# power.net
KiCad netlist of a schematic drawn in Altium Designer
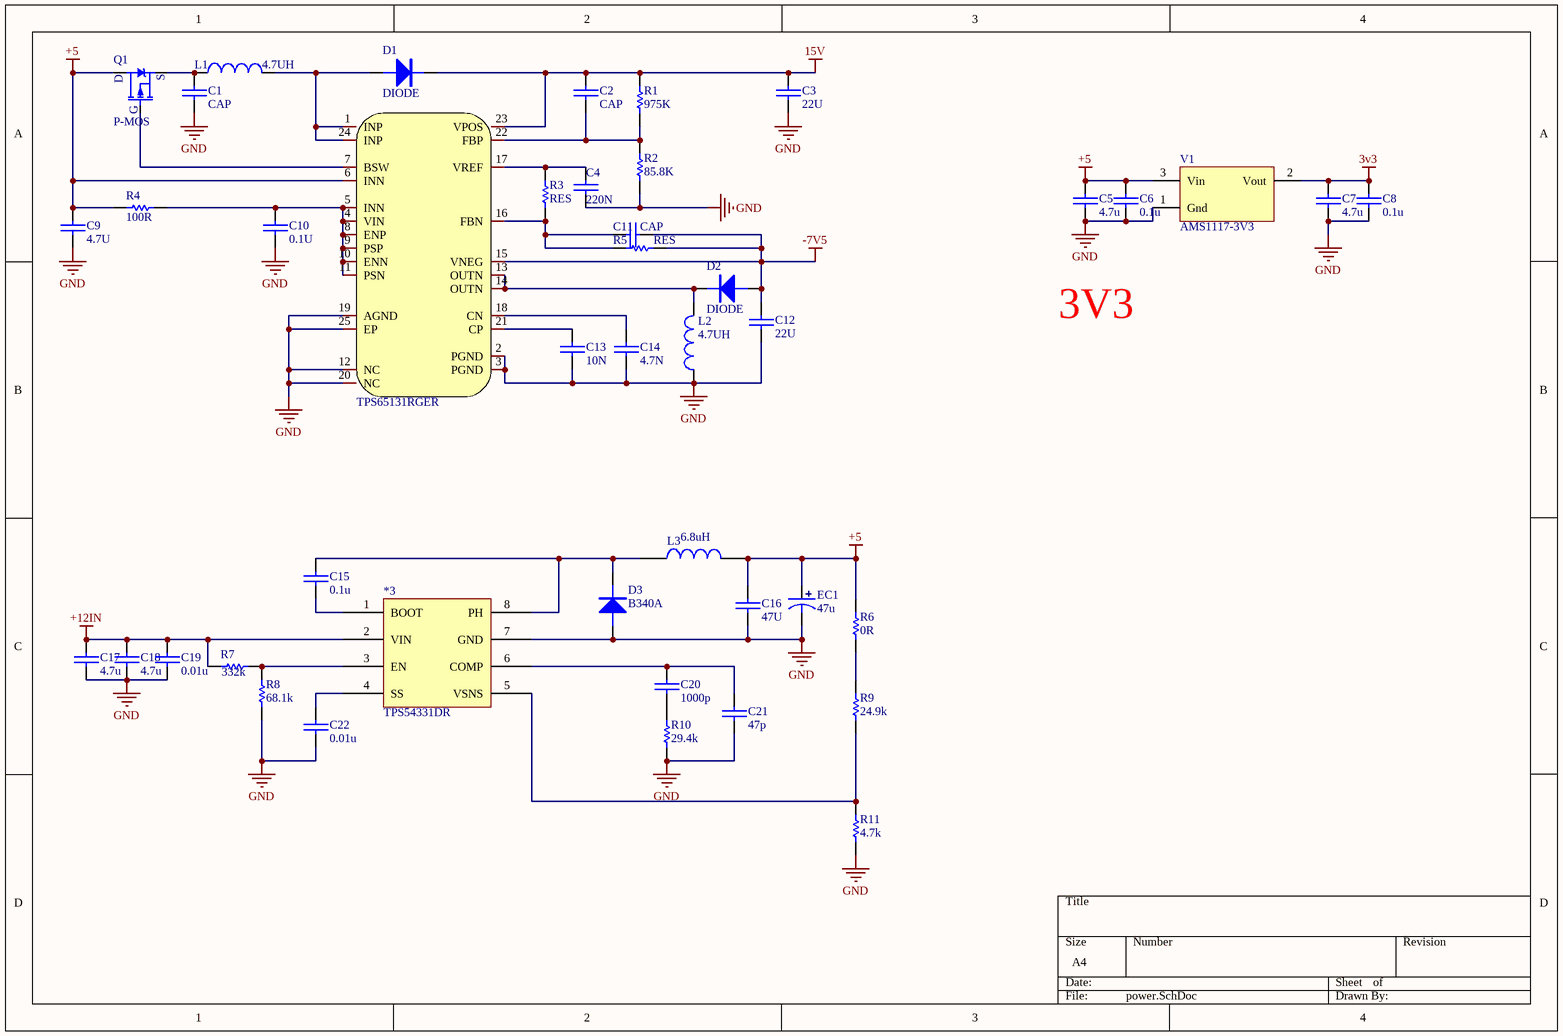
[diagram p0: power.SchDoc]

(export (version "E")
  (design (tool "Eeschema 10.0.6"))
  (components
    (comp (ref "*3")
      (value "TPS54331DR")
      (footprint "SOIC-8")
      (description "降压型DC-DC")
      (libsource (lib "0.03电源") (part "TPS54331DR"))
    )
    (comp (ref "C1")
      (value "CAP")
      (footprint "0603C")
      (description "无极性电容")
      (libsource (lib "1.00-阻容感") (part "CAP"))
    )
    (comp (ref "C2")
      (value "CAP")
      (footprint "0603C")
      (description "无极性电容")
      (libsource (lib "1.00-阻容感") (part "CAP"))
    )
    (comp (ref "C3")
      (value "22U")
      (footprint "0603C")
      (description "无极性电容")
      (libsource (lib "1.00-阻容感") (part "CAP"))
    )
    (comp (ref "C4")
      (value "220N")
      (footprint "0603C")
      (description "无极性电容")
      (libsource (lib "1.00-阻容感") (part "CAP"))
    )
    (comp (ref "C5")
      (value "4.7u")
      (footprint "0603C")
      (description "无极性电容")
      (libsource (lib "1.00-阻容感") (part "CAP"))
    )
    (comp (ref "C6")
      (value "0.1u")
      (footprint "0603C")
      (description "无极性电容")
      (libsource (lib "1.00-阻容感") (part "CAP"))
    )
    (comp (ref "C7")
      (value "4.7u")
      (footprint "0603C")
      (description "无极性电容")
      (libsource (lib "1.00-阻容感") (part "CAP"))
    )
    (comp (ref "C8")
      (value "0.1u")
      (footprint "0603C")
      (description "无极性电容")
      (libsource (lib "1.00-阻容感") (part "CAP"))
    )
    (comp (ref "C9")
      (value "4.7U")
      (footprint "0603C")
      (description "无极性电容")
      (libsource (lib "1.00-阻容感") (part "CAP"))
    )
    (comp (ref "C10")
      (value "0.1U")
      (footprint "0603C")
      (description "无极性电容")
      (libsource (lib "1.00-阻容感") (part "CAP"))
    )
    (comp (ref "C11")
      (value "CAP")
      (footprint "0603C")
      (description "无极性电容")
      (libsource (lib "1.00-阻容感") (part "CAP"))
    )
    (comp (ref "C12")
      (value "22U")
      (footprint "0603C")
      (description "无极性电容")
      (libsource (lib "1.00-阻容感") (part "CAP"))
    )
    (comp (ref "C13")
      (value "10N")
      (footprint "0603C")
      (description "无极性电容")
      (libsource (lib "1.00-阻容感") (part "CAP"))
    )
    (comp (ref "C14")
      (value "4.7N")
      (footprint "0603C")
      (description "无极性电容")
      (libsource (lib "1.00-阻容感") (part "CAP"))
    )
    (comp (ref "C15")
      (value "0.1u")
      (footprint "0603C")
      (description "无极性电容")
      (libsource (lib "1.00-阻容感") (part "CAP"))
    )
    (comp (ref "C16")
      (value "47U")
      (footprint "0603C")
      (description "无极性电容")
      (libsource (lib "1.00-阻容感") (part "CAP"))
    )
    (comp (ref "C17")
      (value "4.7u")
      (footprint "0603C")
      (description "无极性电容")
      (libsource (lib "1.00-阻容感") (part "CAP"))
    )
    (comp (ref "C18")
      (value "4.7u")
      (footprint "0603C")
      (description "无极性电容")
      (libsource (lib "1.00-阻容感") (part "CAP"))
    )
    (comp (ref "C19")
      (value "0.01u")
      (footprint "0603C")
      (description "无极性电容")
      (libsource (lib "1.00-阻容感") (part "CAP"))
    )
    (comp (ref "C20")
      (value "1000p")
      (footprint "0603C")
      (description "无极性电容")
      (libsource (lib "1.00-阻容感") (part "CAP"))
    )
    (comp (ref "C21")
      (value "47p")
      (footprint "0603C")
      (description "无极性电容")
      (libsource (lib "1.00-阻容感") (part "CAP"))
    )
    (comp (ref "C22")
      (value "0.01u")
      (footprint "0603C")
      (description "无极性电容")
      (libsource (lib "1.00-阻容感") (part "CAP"))
    )
    (comp (ref "D1")
      (value "DIODE")
      (footprint "SOD-123")
      (description "普通二极管")
      (libsource (lib "2.00-二极管") (part "DIODE"))
    )
    (comp (ref "D2")
      (value "DIODE")
      (footprint "SOD-123")
      (description "普通二极管")
      (libsource (lib "2.00-二极管") (part "DIODE"))
    )
    (comp (ref "D3")
      (value "B340A")
      (footprint "SMA/DO-214AC")
      (description "普通二极管")
      (libsource (lib "2.00-二极管") (part "DIODE"))
    )
    (comp (ref "EC1")
      (value "47u")
      (footprint "SMD-EC6.3X6.3X10")
      (description "贴片电解电容")
      (libsource (lib "1.00-阻容感") (part "ECAP"))
    )
    (comp (ref "L1")
      (value "4.7UH")
      (footprint "L-SMD-0420")
      (description "小功率贴片电感")
      (libsource (lib "1.00-阻容感") (part "L"))
    )
    (comp (ref "L2")
      (value "4.7UH")
      (footprint "L-SMD-0420")
      (description "小功率贴片电感")
      (libsource (lib "") (part "L_2"))
    )
    (comp (ref "L3")
      (value "6.8uH")
      (footprint "L-SMD-0630")
      (description "INDUCTOR")
      (libsource (lib "") (part "L_1"))
    )
    (comp (ref "Q1")
      (value "P-MOS")
      (footprint "SOT23")
      (description "P沟道场效应管")
      (libsource (lib "3.01-MOS管") (part "P-MOS"))
    )
    (comp (ref "R1")
      (value "975K")
      (footprint "0603R")
      (description "电阻")
      (libsource (lib "1.00-阻容感") (part "RES"))
    )
    (comp (ref "R2")
      (value "85.8K")
      (footprint "0603R")
      (description "电阻")
      (libsource (lib "1.00-阻容感") (part "RES"))
    )
    (comp (ref "R3")
      (value "RES")
      (footprint "0603R")
      (description "电阻")
      (libsource (lib "1.00-阻容感") (part "RES"))
    )
    (comp (ref "R4")
      (value "100R")
      (footprint "0603R")
      (description "电阻")
      (libsource (lib "1.00-阻容感") (part "RES"))
    )
    (comp (ref "R5")
      (value "RES")
      (footprint "0603R")
      (description "电阻")
      (libsource (lib "1.00-阻容感") (part "RES"))
    )
    (comp (ref "R6")
      (value "0R")
      (footprint "0603R")
      (description "电阻")
      (libsource (lib "1.00-阻容感") (part "RES"))
    )
    (comp (ref "R7")
      (value "332k")
      (footprint "0603R")
      (description "电阻")
      (libsource (lib "1.00-阻容感") (part "RES"))
    )
    (comp (ref "R8")
      (value "68.1k")
      (footprint "0603R")
      (description "电阻")
      (libsource (lib "1.00-阻容感") (part "RES"))
    )
    (comp (ref "R9")
      (value "24.9k")
      (footprint "0603R")
      (description "电阻")
      (libsource (lib "1.00-阻容感") (part "RES"))
    )
    (comp (ref "R10")
      (value "29.4k")
      (footprint "0603R")
      (description "电阻")
      (libsource (lib "1.00-阻容感") (part "RES"))
    )
    (comp (ref "R11")
      (value "4.7k")
      (footprint "0603R")
      (description "电阻")
      (libsource (lib "1.00-阻容感") (part "RES"))
    )
    (comp (ref "U1")
      (value "TPS65131RGER")
      (footprint "QFN-24_L4.0-W4.0-P0.50-TL-EP2.6")
      (description "具有正负（双路）输出的 1950mA 升压电流，用于 OLED 和 CCD 传感器")
      (fields (field (name "MANUFACTURER") "TI(德州仪器)"))
      (libsource (lib "0.03电源") (part "TPS65131RGER"))
    )
    (comp (ref "V1")
      (value "AMS1117-3V3")
      (footprint "SOT223_L")
      (description "LDO")
      (libsource (lib "0.03电源") (part "AMS1117"))
    )
  )
  (nets
    (net (code "1") (name "+5") (class "Default")
      (node (ref "C16") (pin "2") (pinfunction "2_2") (pintype "passive"))
      (node (ref "C5") (pin "2") (pinfunction "2_2") (pintype "passive"))
      (node (ref "C6") (pin "2") (pinfunction "2_2") (pintype "passive"))
      (node (ref "C9") (pin "2") (pinfunction "2_2") (pintype "passive"))
      (node (ref "EC1") (pin "1") (pinfunction "1_1") (pintype "passive"))
      (node (ref "L3") (pin "2") (pinfunction "2_2") (pintype "passive"))
      (node (ref "Q1") (pin "3") (pinfunction "D_3") (pintype "passive"))
      (node (ref "R4") (pin "2") (pinfunction "2_2") (pintype "passive"))
      (node (ref "R6") (pin "2") (pinfunction "2_2") (pintype "passive"))
      (node (ref "U1") (pin "6") (pinfunction "INN_6") (pintype "passive"))
      (node (ref "V1") (pin "3") (pinfunction "Vin_3") (pintype "passive"))
    )
    (net (code "2") (name "+12IN") (class "Default")
      (node (ref "*3") (pin "2") (pinfunction "VIN_2") (pintype "passive"))
      (node (ref "C17") (pin "2") (pinfunction "2_2") (pintype "passive"))
      (node (ref "C18") (pin "2") (pinfunction "2_2") (pintype "passive"))
      (node (ref "C19") (pin "2") (pinfunction "2_2") (pintype "passive"))
      (node (ref "R7") (pin "2") (pinfunction "2_2") (pintype "passive"))
    )
    (net (code "3") (name "-7V5") (class "Default")
      (node (ref "C11") (pin "1") (pinfunction "1_1") (pintype "passive"))
      (node (ref "C12") (pin "1") (pinfunction "1_1") (pintype "passive"))
      (node (ref "D2") (pin "A") (pinfunction "A_A") (pintype "passive"))
      (node (ref "R5") (pin "1") (pinfunction "1_1") (pintype "passive"))
      (node (ref "U1") (pin "15") (pinfunction "VNEG_15") (pintype "passive"))
    )
    (net (code "4") (name "3v3") (class "Default")
      (node (ref "C7") (pin "2") (pinfunction "2_2") (pintype "passive"))
      (node (ref "C8") (pin "2") (pinfunction "2_2") (pintype "passive"))
      (node (ref "V1") (pin "2") (pinfunction "Vout_2") (pintype "passive"))
    )
    (net (code "5") (name "15V") (class "Default")
      (node (ref "C2") (pin "2") (pinfunction "2_2") (pintype "passive"))
      (node (ref "C3") (pin "2") (pinfunction "2_2") (pintype "passive"))
      (node (ref "D1") (pin "K") (pinfunction "K_K") (pintype "passive"))
      (node (ref "R1") (pin "2") (pinfunction "2_2") (pintype "passive"))
      (node (ref "U1") (pin "23") (pinfunction "VPOS_23") (pintype "passive"))
    )
    (net (code "6") (name "GND") (class "Default")
      (node (ref "*3") (pin "7") (pinfunction "GND_7") (pintype "passive"))
      (node (ref "C1") (pin "1") (pinfunction "1_1") (pintype "passive"))
      (node (ref "C10") (pin "1") (pinfunction "1_1") (pintype "passive"))
      (node (ref "C12") (pin "2") (pinfunction "2_2") (pintype "passive"))
      (node (ref "C13") (pin "2") (pinfunction "2_2") (pintype "passive"))
      (node (ref "C14") (pin "2") (pinfunction "2_2") (pintype "passive"))
      (node (ref "C16") (pin "1") (pinfunction "1_1") (pintype "passive"))
      (node (ref "C17") (pin "1") (pinfunction "1_1") (pintype "passive"))
      (node (ref "C18") (pin "1") (pinfunction "1_1") (pintype "passive"))
      (node (ref "C19") (pin "1") (pinfunction "1_1") (pintype "passive"))
      (node (ref "C21") (pin "1") (pinfunction "1_1") (pintype "passive"))
      (node (ref "C22") (pin "1") (pinfunction "1_1") (pintype "passive"))
      (node (ref "C3") (pin "1") (pinfunction "1_1") (pintype "passive"))
      (node (ref "C4") (pin "1") (pinfunction "1_1") (pintype "passive"))
      (node (ref "C5") (pin "1") (pinfunction "1_1") (pintype "passive"))
      (node (ref "C6") (pin "1") (pinfunction "1_1") (pintype "passive"))
      (node (ref "C7") (pin "1") (pinfunction "1_1") (pintype "passive"))
      (node (ref "C8") (pin "1") (pinfunction "1_1") (pintype "passive"))
      (node (ref "C9") (pin "1") (pinfunction "1_1") (pintype "passive"))
      (node (ref "D3") (pin "A") (pinfunction "A_A") (pintype "passive"))
      (node (ref "EC1") (pin "2") (pinfunction "2_2") (pintype "passive"))
      (node (ref "L2") (pin "1") (pinfunction "1_1") (pintype "passive"))
      (node (ref "R10") (pin "1") (pinfunction "1_1") (pintype "passive"))
      (node (ref "R11") (pin "1") (pinfunction "1_1") (pintype "passive"))
      (node (ref "R2") (pin "1") (pinfunction "1_1") (pintype "passive"))
      (node (ref "R8") (pin "1") (pinfunction "1_1") (pintype "passive"))
      (node (ref "U1") (pin "12") (pinfunction "NC_12") (pintype "passive"))
      (node (ref "U1") (pin "19") (pinfunction "AGND_19") (pintype "passive"))
      (node (ref "U1") (pin "2") (pinfunction "PGND_2") (pintype "passive"))
      (node (ref "U1") (pin "20") (pinfunction "NC_20") (pintype "passive"))
      (node (ref "U1") (pin "25") (pinfunction "EP_25") (pintype "passive"))
      (node (ref "U1") (pin "3") (pinfunction "PGND_3") (pintype "passive"))
      (node (ref "V1") (pin "1") (pinfunction "Gnd_1") (pintype "passive"))
    )
    (net (code "7") (name "Net-(*3-BOOT)") (class "Default")
      (node (ref "*3") (pin "1") (pinfunction "BOOT_1") (pintype "passive"))
      (node (ref "C15") (pin "1") (pinfunction "1_1") (pintype "passive"))
    )
    (net (code "8") (name "Net-(*3-COMP)") (class "Default")
      (node (ref "*3") (pin "6") (pinfunction "COMP_6") (pintype "passive"))
      (node (ref "C20") (pin "2") (pinfunction "2_2") (pintype "passive"))
      (node (ref "C21") (pin "2") (pinfunction "2_2") (pintype "passive"))
    )
    (net (code "9") (name "Net-(*3-EN)") (class "Default")
      (node (ref "*3") (pin "3") (pinfunction "EN_3") (pintype "passive"))
      (node (ref "R7") (pin "1") (pinfunction "1_1") (pintype "passive"))
      (node (ref "R8") (pin "2") (pinfunction "2_2") (pintype "passive"))
    )
    (net (code "10") (name "Net-(*3-PH)") (class "Default")
      (node (ref "*3") (pin "8") (pinfunction "PH_8") (pintype "passive"))
      (node (ref "C15") (pin "2") (pinfunction "2_2") (pintype "passive"))
      (node (ref "D3") (pin "K") (pinfunction "K_K") (pintype "passive"))
      (node (ref "L3") (pin "1") (pinfunction "1_1") (pintype "passive"))
    )
    (net (code "11") (name "Net-(*3-SS)") (class "Default")
      (node (ref "*3") (pin "4") (pinfunction "SS_4") (pintype "passive"))
      (node (ref "C22") (pin "2") (pinfunction "2_2") (pintype "passive"))
    )
    (net (code "12") (name "Net-(*3-VSNS)") (class "Default")
      (node (ref "*3") (pin "5") (pinfunction "VSNS_5") (pintype "passive"))
      (node (ref "R11") (pin "2") (pinfunction "2_2") (pintype "passive"))
      (node (ref "R9") (pin "1") (pinfunction "1_1") (pintype "passive"))
    )
    (net (code "13") (name "Net-(C20-Pad1)") (class "Default")
      (node (ref "C20") (pin "1") (pinfunction "1_1") (pintype "passive"))
      (node (ref "R10") (pin "2") (pinfunction "2_2") (pintype "passive"))
    )
    (net (code "14") (name "Net-(D1-PadA)") (class "Default")
      (node (ref "D1") (pin "A") (pinfunction "A_A") (pintype "passive"))
      (node (ref "L1") (pin "2") (pinfunction "2_2") (pintype "passive"))
      (node (ref "U1") (pin "1") (pinfunction "INP_1") (pintype "passive"))
      (node (ref "U1") (pin "24") (pinfunction "INP_24") (pintype "passive"))
    )
    (net (code "15") (name "Net-(D2-PadK)") (class "Default")
      (node (ref "D2") (pin "K") (pinfunction "K_K") (pintype "passive"))
      (node (ref "L2") (pin "2") (pinfunction "2_2") (pintype "passive"))
      (node (ref "U1") (pin "13") (pinfunction "OUTN_13") (pintype "passive"))
      (node (ref "U1") (pin "14") (pinfunction "OUTN_14") (pintype "passive"))
    )
    (net (code "16") (name "Net-(Q1-G)") (class "Default")
      (node (ref "Q1") (pin "1") (pinfunction "G_1") (pintype "passive"))
      (node (ref "U1") (pin "7") (pinfunction "BSW_7") (pintype "passive"))
    )
    (net (code "17") (name "Net-(Q1-S)") (class "Default")
      (node (ref "C1") (pin "2") (pinfunction "2_2") (pintype "passive"))
      (node (ref "L1") (pin "1") (pinfunction "1_1") (pintype "passive"))
      (node (ref "Q1") (pin "2") (pinfunction "S_2") (pintype "passive"))
    )
    (net (code "18") (name "Net-(R6-Pad1)") (class "Default")
      (node (ref "R6") (pin "1") (pinfunction "1_1") (pintype "passive"))
      (node (ref "R9") (pin "2") (pinfunction "2_2") (pintype "passive"))
    )
    (net (code "19") (name "Net-(U1-CN)") (class "Default")
      (node (ref "C14") (pin "1") (pinfunction "1_1") (pintype "passive"))
      (node (ref "U1") (pin "18") (pinfunction "CN_18") (pintype "passive"))
    )
    (net (code "20") (name "Net-(U1-CP)") (class "Default")
      (node (ref "C13") (pin "1") (pinfunction "1_1") (pintype "passive"))
      (node (ref "U1") (pin "21") (pinfunction "CP_21") (pintype "passive"))
    )
    (net (code "21") (name "Net-(U1-ENN)") (class "Default")
      (node (ref "C10") (pin "2") (pinfunction "2_2") (pintype "passive"))
      (node (ref "R4") (pin "1") (pinfunction "1_1") (pintype "passive"))
      (node (ref "U1") (pin "10") (pinfunction "ENN_10") (pintype "passive"))
      (node (ref "U1") (pin "11") (pinfunction "PSN_11") (pintype "passive"))
      (node (ref "U1") (pin "4") (pinfunction "VIN_4") (pintype "passive"))
      (node (ref "U1") (pin "5") (pinfunction "INN_5") (pintype "passive"))
      (node (ref "U1") (pin "8") (pinfunction "ENP_8") (pintype "passive"))
      (node (ref "U1") (pin "9") (pinfunction "PSP_9") (pintype "passive"))
    )
    (net (code "22") (name "Net-(U1-FBN)") (class "Default")
      (node (ref "C11") (pin "2") (pinfunction "2_2") (pintype "passive"))
      (node (ref "R3") (pin "1") (pinfunction "1_1") (pintype "passive"))
      (node (ref "R5") (pin "2") (pinfunction "2_2") (pintype "passive"))
      (node (ref "U1") (pin "16") (pinfunction "FBN_16") (pintype "passive"))
    )
    (net (code "23") (name "Net-(U1-FBP)") (class "Default")
      (node (ref "C2") (pin "1") (pinfunction "1_1") (pintype "passive"))
      (node (ref "R1") (pin "1") (pinfunction "1_1") (pintype "passive"))
      (node (ref "R2") (pin "2") (pinfunction "2_2") (pintype "passive"))
      (node (ref "U1") (pin "22") (pinfunction "FBP_22") (pintype "passive"))
    )
    (net (code "24") (name "Net-(U1-VREF)") (class "Default")
      (node (ref "C4") (pin "2") (pinfunction "2_2") (pintype "passive"))
      (node (ref "R3") (pin "2") (pinfunction "2_2") (pintype "passive"))
      (node (ref "U1") (pin "17") (pinfunction "VREF_17") (pintype "passive"))
    )
  )
)
